# LDO.net
KiCad netlist of a schematic drawn in Altium Designer
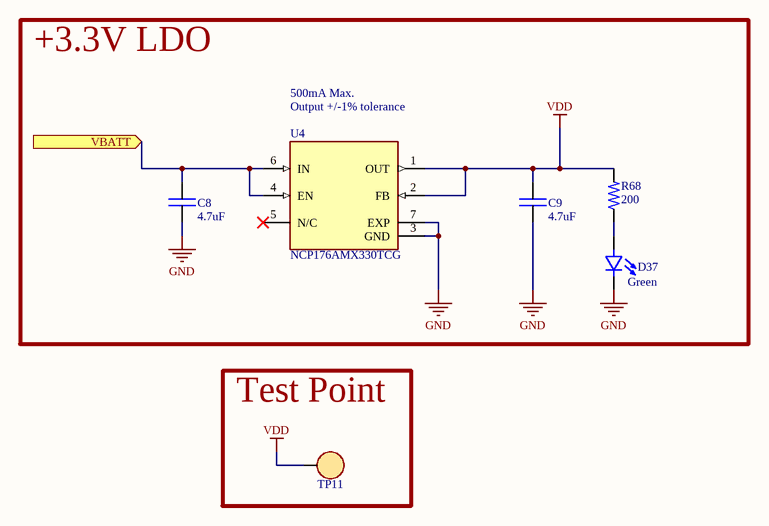
[diagram p0: LDO.SchDoc]

(export (version "E")
  (design (tool "Eeschema 10.0.6"))
  (components
    (comp (ref "C8")
      (value "4.7uF")
      (footprint "PressurePulse:0402C")
      (description "Capacitor")
      (fields (field (name "Comment") "CAP"))
      (libsource (lib "PressurePulse") (part "CAP"))
    )
    (comp (ref "C9")
      (value "4.7uF")
      (footprint "PressurePulse:0402C")
      (description "Capacitor")
      (fields (field (name "Comment") "CAP"))
      (libsource (lib "PressurePulse") (part "CAP"))
    )
    (comp (ref "D37")
      (value "LED - single")
      (footprint "PressurePulse:0603-LED")
      (description "LED")
      (fields (field (name "COLOR") "Green"))
      (libsource (lib "PressurePulse") (part "LED - single"))
    )
    (comp (ref "R68")
      (value "200")
      (footprint "PressurePulse:0402R")
      (description "Resistor")
      (fields (field (name "Comment") "RES"))
      (libsource (lib "PressurePulse") (part "RES"))
    )
    (comp (ref "TP11")
      (value "RH-5019")
      (footprint "PressurePulse:TP - RH-5019")
      (fields (field (name "MFR") "ronghe"))
      (libsource (lib "PressurePulse") (part "TEST POINT"))
    )
    (comp (ref "U4")
      (value "NCP176AMX330TCG")
      (footprint "PressurePulse:6-XDFN")
      (description "LDO REGULATOR")
      (fields (field (name "MFR") "onsemi"))
      (libsource (lib "PressurePulse") (part "LDO 3.3V"))
    )
  )
  (nets
    (net (code "1") (name "/VBATT") (class "Default")
      (node (ref "C8") (pin "2") (pinfunction "2_2") (pintype "passive"))
      (node (ref "U4") (pin "4") (pinfunction "EN_4") (pintype "input"))
      (node (ref "U4") (pin "6") (pinfunction "IN_6") (pintype "input"))
    )
    (net (code "2") (name "GND") (class "Default")
      (node (ref "C8") (pin "1") (pinfunction "1_1") (pintype "passive"))
      (node (ref "C9") (pin "1") (pinfunction "1_1") (pintype "passive"))
      (node (ref "D37") (pin "2") (pinfunction "C_2") (pintype "passive"))
      (node (ref "U4") (pin "3") (pinfunction "GND_3") (pintype "power_in"))
      (node (ref "U4") (pin "7") (pinfunction "EXP_7") (pintype "power_in"))
    )
    (net (code "3") (name "Net-(D37-A)") (class "Default")
      (node (ref "D37") (pin "1") (pinfunction "A_1") (pintype "passive"))
      (node (ref "R68") (pin "1") (pinfunction "1_1") (pintype "passive"))
    )
    (net (code "4") (name "VDD") (class "Default")
      (node (ref "C9") (pin "2") (pinfunction "2_2") (pintype "passive"))
      (node (ref "R68") (pin "2") (pinfunction "2_2") (pintype "passive"))
      (node (ref "TP11") (pin "1") (pinfunction "1_1") (pintype "passive"))
      (node (ref "U4") (pin "1") (pinfunction "OUT_1") (pintype "output"))
      (node (ref "U4") (pin "2") (pinfunction "FB_2") (pintype "input"))
    )
    (net (code "5") (name "unconnected-(U4-N{slash}C-Pad5)") (class "Default")
      (node (ref "U4") (pin "5") (pinfunction "N/C_5") (pintype "passive+no_connect"))
    )
  )
)
